# encoder.net
KiCad netlist of a schematic drawn in EAGLE
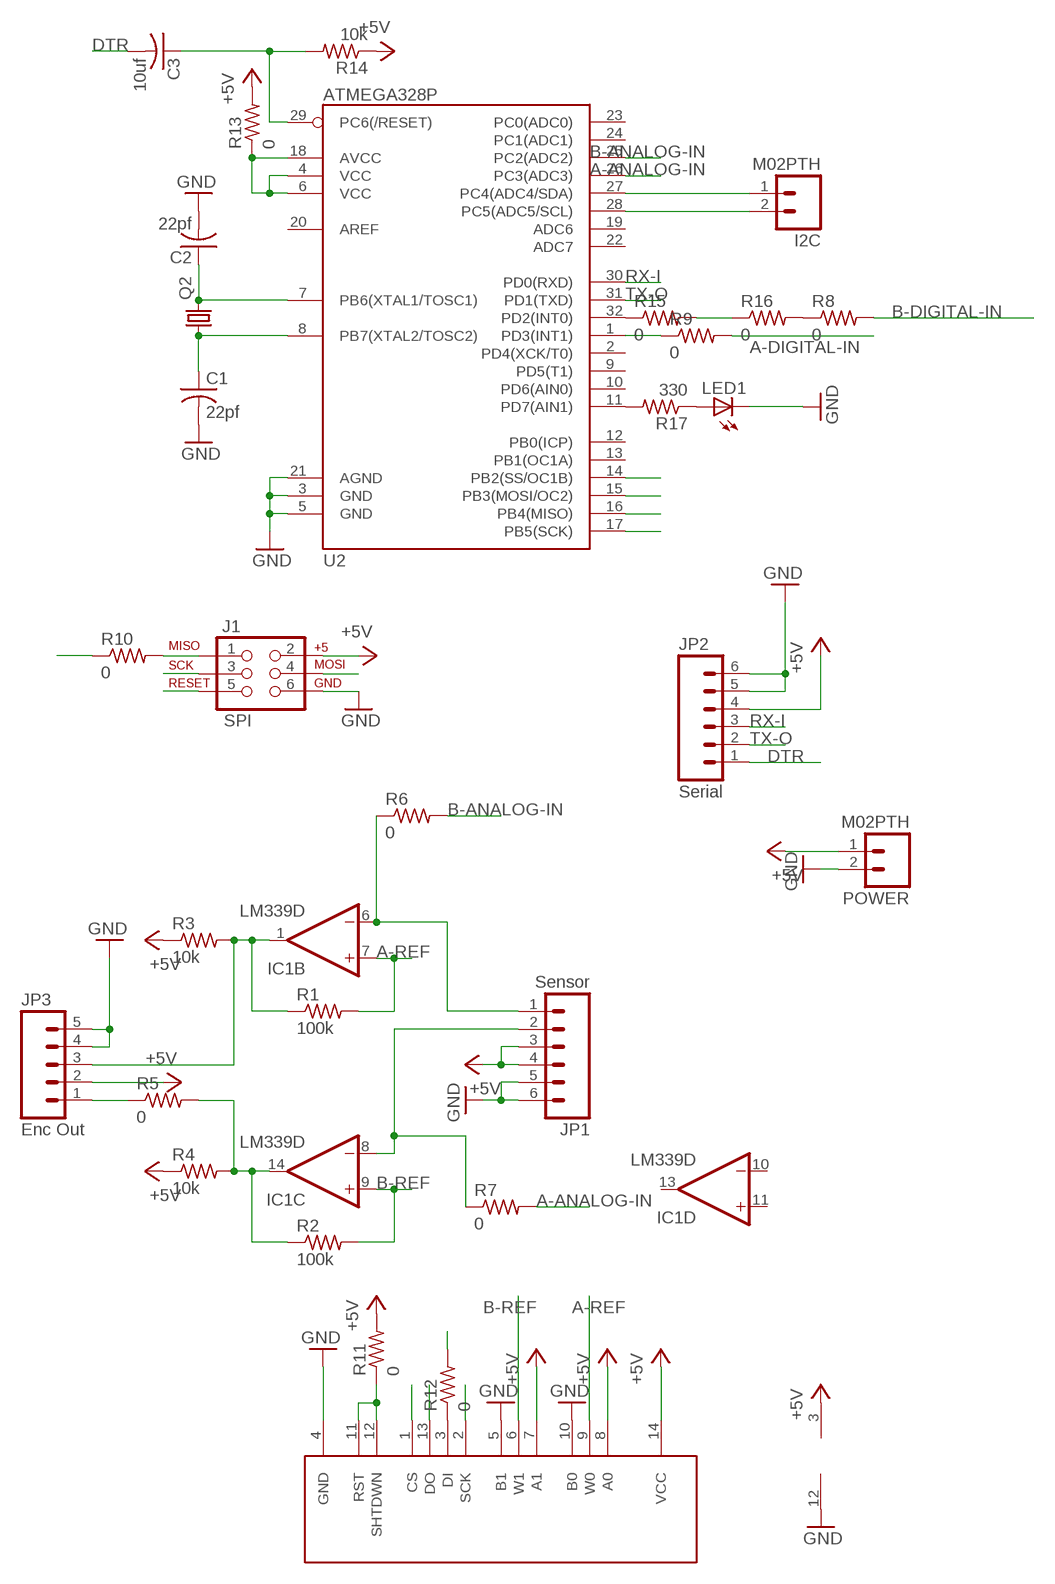
[diagram p0: schematic, sheet 1]

(export (version "E")
  (design (tool "Eeschema 10.0.6"))
  (components
    (comp (ref "C1")
      (value "22pf")
      (footprint "eagle-import:C1206")
      (libsource (lib "eagle-import") (part "C-USC1206"))
    )
    (comp (ref "C2")
      (value "22pf")
      (footprint "eagle-import:C1206")
      (libsource (lib "eagle-import") (part "C-USC1206"))
    )
    (comp (ref "C3")
      (value "10uf")
      (footprint "eagle-import:C1206")
      (libsource (lib "eagle-import") (part "C-USC1206"))
    )
    (comp (ref "I2C")
      (value "M02PTH")
      (footprint "eagle-import:1X02")
      (libsource (lib "eagle-import") (part "M02PTH"))
    )
    (comp (ref "IC1")
      (value "LM339D")
      (footprint "eagle-import:SO14")
      (libsource (lib "eagle-import") (part "LM339D"))
    )
    (comp (ref "J1")
      (value "SPI")
      (footprint "eagle-import:2X3-NS")
      (libsource (lib "eagle-import") (part "AVR_SPI_PRG_6NS"))
    )
    (comp (ref "JP1")
      (value "Sensor")
      (footprint "eagle-import:1X06")
      (libsource (lib "eagle-import") (part "M06SIP"))
    )
    (comp (ref "JP2")
      (value "Serial")
      (footprint "eagle-import:1X06")
      (libsource (lib "eagle-import") (part "M06SIP"))
    )
    (comp (ref "JP3")
      (value "Enc Out")
      (footprint "eagle-import:1X05_NO_SILK")
      (libsource (lib "eagle-import") (part "M05NO_SILK"))
    )
    (comp (ref "LED1")
      (value "LEDSMT1206")
      (footprint "eagle-import:1206")
      (libsource (lib "eagle-import") (part "LEDSMT1206"))
    )
    (comp (ref "POWER")
      (value "M02PTH")
      (footprint "eagle-import:1X02")
      (libsource (lib "eagle-import") (part "M02PTH"))
    )
    (comp (ref "Q2")
      (value "CRYSTALHC49UP")
      (footprint "eagle-import:HC49UP")
      (libsource (lib "eagle-import") (part "CRYSTALHC49UP"))
    )
    (comp (ref "R1")
      (value "100k")
      (footprint "eagle-import:R1206")
      (libsource (lib "eagle-import") (part "R-US_R1206"))
    )
    (comp (ref "R2")
      (value "100k")
      (footprint "eagle-import:R1206")
      (libsource (lib "eagle-import") (part "R-US_R1206"))
    )
    (comp (ref "R3")
      (value "10k")
      (footprint "eagle-import:R1206")
      (libsource (lib "eagle-import") (part "R-US_R1206"))
    )
    (comp (ref "R4")
      (value "10k")
      (footprint "eagle-import:R1206")
      (libsource (lib "eagle-import") (part "R-US_R1206"))
    )
    (comp (ref "R5")
      (value "0")
      (footprint "eagle-import:R1206")
      (libsource (lib "eagle-import") (part "R-US_R1206"))
    )
    (comp (ref "R6")
      (value "0")
      (footprint "eagle-import:R1206")
      (libsource (lib "eagle-import") (part "R-US_R1206"))
    )
    (comp (ref "R7")
      (value "0")
      (footprint "eagle-import:R1206")
      (libsource (lib "eagle-import") (part "R-US_R1206"))
    )
    (comp (ref "R8")
      (value "0")
      (footprint "eagle-import:R1206")
      (libsource (lib "eagle-import") (part "R-US_R1206"))
    )
    (comp (ref "R9")
      (value "0")
      (footprint "eagle-import:R1206")
      (libsource (lib "eagle-import") (part "R-US_R1206"))
    )
    (comp (ref "R10")
      (value "0")
      (footprint "eagle-import:R1206")
      (libsource (lib "eagle-import") (part "R-US_R1206"))
    )
    (comp (ref "R11")
      (value "0")
      (footprint "eagle-import:R1206")
      (libsource (lib "eagle-import") (part "R-US_R1206"))
    )
    (comp (ref "R12")
      (value "0")
      (footprint "eagle-import:R1206")
      (libsource (lib "eagle-import") (part "R-US_R1206"))
    )
    (comp (ref "R13")
      (value "0")
      (footprint "eagle-import:R1206")
      (libsource (lib "eagle-import") (part "R-US_R1206"))
    )
    (comp (ref "R14")
      (value "10k")
      (footprint "eagle-import:R1206")
      (libsource (lib "eagle-import") (part "R-US_R1206"))
    )
    (comp (ref "R15")
      (value "0")
      (footprint "eagle-import:R1206")
      (libsource (lib "eagle-import") (part "R-US_R1206"))
    )
    (comp (ref "R16")
      (value "0")
      (footprint "eagle-import:R1206")
      (libsource (lib "eagle-import") (part "R-US_R1206"))
    )
    (comp (ref "R17")
      (value "330")
      (footprint "eagle-import:R1206")
      (libsource (lib "eagle-import") (part "R-US_R1206"))
    )
    (comp (ref "U1")
      (value "MCP42XXX")
      (footprint "eagle-import:SO014")
      (libsource (lib "eagle-import") (part "MCP42XXX"))
    )
    (comp (ref "U2")
      (value "ATMEGA328P")
      (footprint "eagle-import:TQFP32-08")
      (libsource (lib "eagle-import") (part "ATMEGA328_SMT"))
    )
  )
  (nets
    (net (code "1") (name "+5V") (class "Default")
      (node (ref "IC1") (pin "3") (pinfunction "V+_3") (pintype "power_in"))
      (node (ref "J1") (pin "2") (pinfunction "2_2") (pintype "passive"))
      (node (ref "JP1") (pin "3") (pinfunction "3_3") (pintype "passive"))
      (node (ref "JP1") (pin "4") (pinfunction "4_4") (pintype "passive"))
      (node (ref "JP2") (pin "4") (pinfunction "4_4") (pintype "passive"))
      (node (ref "JP3") (pin "2") (pinfunction "2_2") (pintype "passive"))
      (node (ref "POWER") (pin "1") (pinfunction "1_1") (pintype "passive"))
      (node (ref "R11") (pin "2") (pinfunction "2_2") (pintype "passive"))
      (node (ref "R13") (pin "2") (pinfunction "2_2") (pintype "passive"))
      (node (ref "R14") (pin "1") (pinfunction "1_1") (pintype "passive"))
      (node (ref "R3") (pin "1") (pinfunction "1_1") (pintype "passive"))
      (node (ref "R4") (pin "1") (pinfunction "1_1") (pintype "passive"))
      (node (ref "U1") (pin "14") (pinfunction "VCC_14") (pintype "bidirectional"))
      (node (ref "U1") (pin "7") (pinfunction "A1_7") (pintype "bidirectional"))
      (node (ref "U1") (pin "8") (pinfunction "A0_8") (pintype "bidirectional"))
    )
    (net (code "2") (name "/A-ANALOG-IN") (class "Default")
      (node (ref "R7") (pin "2") (pinfunction "2_2") (pintype "passive"))
      (node (ref "U2") (pin "26") (pinfunction "PC3(ADC3)_26") (pintype "bidirectional"))
    )
    (net (code "3") (name "/A-DIGITAL-IN") (class "Default")
      (node (ref "IC1") (pin "1") (pinfunction "OUT_1") (pintype "open_collector"))
      (node (ref "JP3") (pin "3") (pinfunction "3_3") (pintype "passive"))
      (node (ref "R1") (pin "1") (pinfunction "1_1") (pintype "passive"))
      (node (ref "R3") (pin "2") (pinfunction "2_2") (pintype "passive"))
      (node (ref "R9") (pin "2") (pinfunction "2_2") (pintype "passive"))
    )
    (net (code "4") (name "/A-REF") (class "Default")
      (node (ref "IC1") (pin "7") (pinfunction "+IN_7") (pintype "input"))
      (node (ref "R1") (pin "2") (pinfunction "2_2") (pintype "passive"))
      (node (ref "U1") (pin "9") (pinfunction "W0_9") (pintype "bidirectional"))
    )
    (net (code "5") (name "/B-ANALOG-IN") (class "Default")
      (node (ref "R6") (pin "2") (pinfunction "2_2") (pintype "passive"))
      (node (ref "U2") (pin "25") (pinfunction "PC2(ADC2)_25") (pintype "bidirectional"))
    )
    (net (code "6") (name "/B-DIGITAL-IN") (class "Default")
      (node (ref "JP3") (pin "1") (pinfunction "1_1") (pintype "passive"))
      (node (ref "R5") (pin "1") (pinfunction "1_1") (pintype "passive"))
      (node (ref "R8") (pin "2") (pinfunction "2_2") (pintype "passive"))
    )
    (net (code "7") (name "/B-REF") (class "Default")
      (node (ref "IC1") (pin "9") (pinfunction "+IN_9") (pintype "input"))
      (node (ref "R2") (pin "2") (pinfunction "2_2") (pintype "passive"))
      (node (ref "U1") (pin "6") (pinfunction "W1_6") (pintype "bidirectional"))
    )
    (net (code "8") (name "/DTR") (class "Default")
      (node (ref "C3") (pin "2") (pinfunction "2_2") (pintype "passive"))
      (node (ref "JP2") (pin "1") (pinfunction "1_1") (pintype "passive"))
    )
    (net (code "9") (name "/MISO") (class "Default")
      (node (ref "R10") (pin "1") (pinfunction "1_1") (pintype "passive"))
      (node (ref "U1") (pin "13") (pinfunction "DO_13") (pintype "bidirectional"))
      (node (ref "U2") (pin "16") (pinfunction "PB4(MISO)_16") (pintype "bidirectional"))
    )
    (net (code "10") (name "/MOSI") (class "Default")
      (node (ref "J1") (pin "4") (pinfunction "4_4") (pintype "passive"))
      (node (ref "R12") (pin "2") (pinfunction "2_2") (pintype "passive"))
      (node (ref "U2") (pin "15") (pinfunction "PB3(MOSI/OC2)_15") (pintype "bidirectional"))
    )
    (net (code "11") (name "/RESET") (class "Default")
      (node (ref "C3") (pin "1") (pinfunction "1_1") (pintype "passive"))
      (node (ref "J1") (pin "5") (pinfunction "5_5") (pintype "passive"))
      (node (ref "R14") (pin "2") (pinfunction "2_2") (pintype "passive"))
      (node (ref "U2") (pin "29") (pinfunction "PC6(/RESET)_29") (pintype "bidirectional"))
    )
    (net (code "12") (name "/RX-I") (class "Default")
      (node (ref "JP2") (pin "3") (pinfunction "3_3") (pintype "passive"))
      (node (ref "U2") (pin "30") (pinfunction "PD0(RXD)_30") (pintype "bidirectional"))
    )
    (net (code "13") (name "/SCK") (class "Default")
      (node (ref "J1") (pin "3") (pinfunction "3_3") (pintype "passive"))
      (node (ref "U1") (pin "2") (pinfunction "SCK_2") (pintype "bidirectional"))
      (node (ref "U2") (pin "17") (pinfunction "PB5(SCK)_17") (pintype "bidirectional"))
    )
    (net (code "14") (name "/SS") (class "Default")
      (node (ref "U1") (pin "1") (pinfunction "CS_1") (pintype "bidirectional"))
      (node (ref "U2") (pin "14") (pinfunction "PB2(SS/OC1B)_14") (pintype "bidirectional"))
    )
    (net (code "15") (name "/TX-O") (class "Default")
      (node (ref "JP2") (pin "2") (pinfunction "2_2") (pintype "passive"))
      (node (ref "U2") (pin "31") (pinfunction "PD1(TXD)_31") (pintype "bidirectional"))
    )
    (net (code "16") (name "GND") (class "Default")
      (node (ref "C1") (pin "2") (pinfunction "2_2") (pintype "passive"))
      (node (ref "C2") (pin "2") (pinfunction "2_2") (pintype "passive"))
      (node (ref "IC1") (pin "12") (pinfunction "GND_12") (pintype "power_in"))
      (node (ref "J1") (pin "6") (pinfunction "6_6") (pintype "passive"))
      (node (ref "JP1") (pin "5") (pinfunction "5_5") (pintype "passive"))
      (node (ref "JP1") (pin "6") (pinfunction "6_6") (pintype "passive"))
      (node (ref "JP2") (pin "5") (pinfunction "5_5") (pintype "passive"))
      (node (ref "JP2") (pin "6") (pinfunction "6_6") (pintype "passive"))
      (node (ref "JP3") (pin "4") (pinfunction "4_4") (pintype "passive"))
      (node (ref "JP3") (pin "5") (pinfunction "5_5") (pintype "passive"))
      (node (ref "LED1") (pin "C") (pinfunction "C_C") (pintype "passive"))
      (node (ref "POWER") (pin "2") (pinfunction "2_2") (pintype "passive"))
      (node (ref "U1") (pin "10") (pinfunction "B0_10") (pintype "bidirectional"))
      (node (ref "U1") (pin "4") (pinfunction "GND_4") (pintype "bidirectional"))
      (node (ref "U1") (pin "5") (pinfunction "B1_5") (pintype "bidirectional"))
      (node (ref "U2") (pin "21") (pinfunction "AGND_21") (pintype "bidirectional"))
      (node (ref "U2") (pin "3") (pinfunction "GND_3") (pintype "bidirectional"))
      (node (ref "U2") (pin "5") (pinfunction "GND_5") (pintype "bidirectional"))
    )
    (net (code "17") (name "Net-(IC1B--IN)") (class "Default")
      (node (ref "IC1") (pin "6") (pinfunction "-IN_6") (pintype "input"))
      (node (ref "JP1") (pin "1") (pinfunction "1_1") (pintype "passive"))
      (node (ref "R6") (pin "1") (pinfunction "1_1") (pintype "passive"))
    )
    (net (code "18") (name "Net-(IC1C--IN)") (class "Default")
      (node (ref "IC1") (pin "8") (pinfunction "-IN_8") (pintype "input"))
      (node (ref "JP1") (pin "2") (pinfunction "2_2") (pintype "passive"))
      (node (ref "R7") (pin "1") (pinfunction "1_1") (pintype "passive"))
    )
    (net (code "19") (name "Net-(IC1C-OUT)") (class "Default")
      (node (ref "IC1") (pin "14") (pinfunction "OUT_14") (pintype "open_collector"))
      (node (ref "R2") (pin "1") (pinfunction "1_1") (pintype "passive"))
      (node (ref "R4") (pin "2") (pinfunction "2_2") (pintype "passive"))
      (node (ref "R5") (pin "2") (pinfunction "2_2") (pintype "passive"))
    )
    (net (code "20") (name "Net-(J1-Pad1)") (class "Default")
      (node (ref "J1") (pin "1") (pinfunction "1_1") (pintype "passive"))
      (node (ref "R10") (pin "2") (pinfunction "2_2") (pintype "passive"))
    )
    (net (code "21") (name "Net-(LED1-PadA)") (class "Default")
      (node (ref "LED1") (pin "A") (pinfunction "A_A") (pintype "passive"))
      (node (ref "R17") (pin "1") (pinfunction "1_1") (pintype "passive"))
    )
    (net (code "22") (name "Net-(R15-Pad2)") (class "Default")
      (node (ref "R15") (pin "2") (pinfunction "2_2") (pintype "passive"))
      (node (ref "R16") (pin "1") (pinfunction "1_1") (pintype "passive"))
    )
    (net (code "23") (name "Net-(R16-Pad2)") (class "Default")
      (node (ref "R16") (pin "2") (pinfunction "2_2") (pintype "passive"))
      (node (ref "R8") (pin "1") (pinfunction "1_1") (pintype "passive"))
    )
    (net (code "24") (name "Net-(U1-DI)") (class "Default")
      (node (ref "R12") (pin "1") (pinfunction "1_1") (pintype "passive"))
      (node (ref "U1") (pin "3") (pinfunction "DI_3") (pintype "bidirectional"))
    )
    (net (code "25") (name "Net-(U1-RST)") (class "Default")
      (node (ref "R11") (pin "1") (pinfunction "1_1") (pintype "passive"))
      (node (ref "U1") (pin "11") (pinfunction "RST_11") (pintype "bidirectional"))
      (node (ref "U1") (pin "12") (pinfunction "SHTDWN_12") (pintype "bidirectional"))
    )
    (net (code "26") (name "Net-(U2-AVCC)") (class "Default")
      (node (ref "R13") (pin "1") (pinfunction "1_1") (pintype "passive"))
      (node (ref "U2") (pin "18") (pinfunction "AVCC_18") (pintype "bidirectional"))
      (node (ref "U2") (pin "4") (pinfunction "VCC_4") (pintype "bidirectional"))
      (node (ref "U2") (pin "6") (pinfunction "VCC_6") (pintype "bidirectional"))
    )
    (net (code "27") (name "Net-(U2-PB6(XTAL1{slash}TOSC1))") (class "Default")
      (node (ref "C2") (pin "1") (pinfunction "1_1") (pintype "passive"))
      (node (ref "Q2") (pin "2") (pinfunction "2_2") (pintype "passive"))
      (node (ref "U2") (pin "7") (pinfunction "PB6(XTAL1/TOSC1)_7") (pintype "bidirectional"))
    )
    (net (code "28") (name "Net-(U2-PB7(XTAL2{slash}TOSC2))") (class "Default")
      (node (ref "C1") (pin "1") (pinfunction "1_1") (pintype "passive"))
      (node (ref "Q2") (pin "1") (pinfunction "1_1") (pintype "passive"))
      (node (ref "U2") (pin "8") (pinfunction "PB7(XTAL2/TOSC2)_8") (pintype "bidirectional"))
    )
    (net (code "29") (name "Net-(U2-PC4(ADC4{slash}SDA))") (class "Default")
      (node (ref "I2C") (pin "1") (pinfunction "1_1") (pintype "passive"))
      (node (ref "U2") (pin "27") (pinfunction "PC4(ADC4/SDA)_27") (pintype "bidirectional"))
    )
    (net (code "30") (name "Net-(U2-PC5(ADC5{slash}SCL))") (class "Default")
      (node (ref "I2C") (pin "2") (pinfunction "2_2") (pintype "passive"))
      (node (ref "U2") (pin "28") (pinfunction "PC5(ADC5/SCL)_28") (pintype "bidirectional"))
    )
    (net (code "31") (name "Net-(U2-PD2(INT0))") (class "Default")
      (node (ref "R15") (pin "1") (pinfunction "1_1") (pintype "passive"))
      (node (ref "U2") (pin "32") (pinfunction "PD2(INT0)_32") (pintype "bidirectional"))
    )
    (net (code "32") (name "Net-(U2-PD3(INT1))") (class "Default")
      (node (ref "R9") (pin "1") (pinfunction "1_1") (pintype "passive"))
      (node (ref "U2") (pin "1") (pinfunction "PD3(INT1)_1") (pintype "bidirectional"))
    )
    (net (code "33") (name "Net-(U2-PD7(AIN1))") (class "Default")
      (node (ref "R17") (pin "2") (pinfunction "2_2") (pintype "passive"))
      (node (ref "U2") (pin "11") (pinfunction "PD7(AIN1)_11") (pintype "bidirectional"))
    )
    (net (code "34") (name "unconnected-(IC1D-+IN-Pad11)") (class "Default")
      (node (ref "IC1") (pin "11") (pinfunction "+IN_11") (pintype "input"))
    )
    (net (code "35") (name "unconnected-(IC1D--IN-Pad10)") (class "Default")
      (node (ref "IC1") (pin "10") (pinfunction "-IN_10") (pintype "input"))
    )
    (net (code "36") (name "unconnected-(IC1D-OUT-Pad13)") (class "Default")
      (node (ref "IC1") (pin "13") (pinfunction "OUT_13") (pintype "open_collector"))
    )
    (net (code "37") (name "unconnected-(U2-ADC6-Pad19)") (class "Default")
      (node (ref "U2") (pin "19") (pinfunction "ADC6_19") (pintype "bidirectional"))
    )
    (net (code "38") (name "unconnected-(U2-ADC7-Pad22)") (class "Default")
      (node (ref "U2") (pin "22") (pinfunction "ADC7_22") (pintype "bidirectional"))
    )
    (net (code "39") (name "unconnected-(U2-AREF-Pad20)") (class "Default")
      (node (ref "U2") (pin "20") (pinfunction "AREF_20") (pintype "bidirectional"))
    )
    (net (code "40") (name "unconnected-(U2-PB0(ICP)-Pad12)") (class "Default")
      (node (ref "U2") (pin "12") (pinfunction "PB0(ICP)_12") (pintype "bidirectional"))
    )
    (net (code "41") (name "unconnected-(U2-PB1(OC1A)-Pad13)") (class "Default")
      (node (ref "U2") (pin "13") (pinfunction "PB1(OC1A)_13") (pintype "bidirectional"))
    )
    (net (code "42") (name "unconnected-(U2-PC0(ADC0)-Pad23)") (class "Default")
      (node (ref "U2") (pin "23") (pinfunction "PC0(ADC0)_23") (pintype "bidirectional"))
    )
    (net (code "43") (name "unconnected-(U2-PC1(ADC1)-Pad24)") (class "Default")
      (node (ref "U2") (pin "24") (pinfunction "PC1(ADC1)_24") (pintype "bidirectional"))
    )
    (net (code "44") (name "unconnected-(U2-PD4(XCK{slash}T0)-Pad2)") (class "Default")
      (node (ref "U2") (pin "2") (pinfunction "PD4(XCK/T0)_2") (pintype "bidirectional"))
    )
    (net (code "45") (name "unconnected-(U2-PD5(T1)-Pad9)") (class "Default")
      (node (ref "U2") (pin "9") (pinfunction "PD5(T1)_9") (pintype "bidirectional"))
    )
    (net (code "46") (name "unconnected-(U2-PD6(AIN0)-Pad10)") (class "Default")
      (node (ref "U2") (pin "10") (pinfunction "PD6(AIN0)_10") (pintype "bidirectional"))
    )
  )
)
